# LNA.net
KiCad netlist of a schematic drawn in Altium Designer
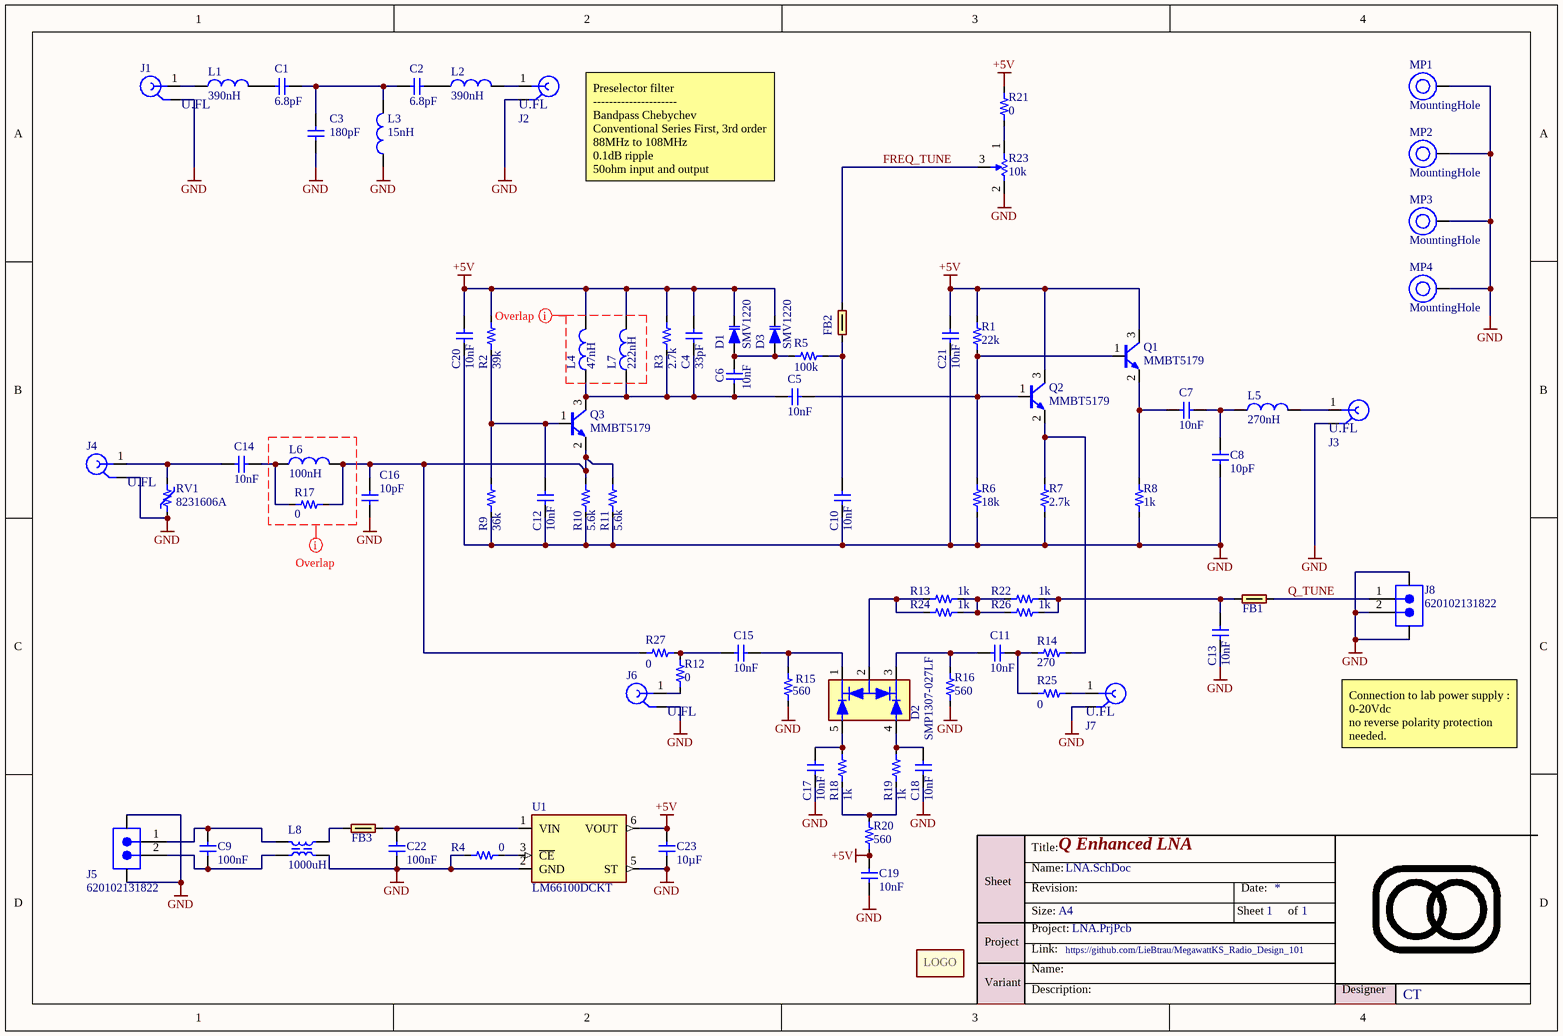
[diagram p0: LNA.SchDoc]

(export (version "E")
  (design (tool "Eeschema 10.0.6"))
  (components
    (comp (ref "C1")
      (value "6.8pF")
      (footprint "0603-C-N")
      (description "WCAP-CSGP Multilayer Ceramic Chip Capacitor, General Purpose, size 0603, NP0, 6.8pF, 50VDC")
      (fields
        (field (name "TOLERANCE") "0.5pF")
        (field (name "Comment") "Capacitor 6.8pF +/-0.5pF 50V NP0 0603")
      )
      (libsource (lib "7c7 Engineering") (part "CAP-NP-2"))
    )
    (comp (ref "C2")
      (value "6.8pF")
      (footprint "0603-C-N")
      (description "WCAP-CSGP Multilayer Ceramic Chip Capacitor, General Purpose, size 0603, NP0, 6.8pF, 50VDC")
      (fields
        (field (name "TOLERANCE") "0.5pF")
        (field (name "Comment") "Capacitor 6.8pF +/-0.5pF 50V NP0 0603")
      )
      (libsource (lib "7c7 Engineering") (part "CAP-NP-2"))
    )
    (comp (ref "C3")
      (value "180pF")
      (footprint "0603-C-N")
      (description "Cap Ceramic 180pF 100V C0G 5% SMD 0603 125°C Paper T/R")
      (fields (field (name "TOLERANCE") "5%") (field (name "JLCPCB PART #") "C107041"))
      (libsource (lib "7c7 Engineering") (part "CAP-NP-2"))
    )
    (comp (ref "C4")
      (value "33pF")
      (footprint "0603-C-N")
      (description "WCAP-CSGP Multilayer Ceramic Chip Capacitor, General Purpose, size 0603, NP0, 33pF, 50VDC")
      (fields (field (name "TOLERANCE") "5%") (field (name "Comment") "Capacitor 33pF +/-5% 50V NP0 0603"))
      (libsource (lib "7c7 Engineering") (part "CAP-NP-2"))
    )
    (comp (ref "C5")
      (value "10nF")
      (footprint "0603-C-N")
      (description "Multilayer Ceramic Capacitor, Grm Series, 0.01 F, 5%, C0g / Np0, 50 V, 0603 [1608 Metric]")
      (fields (field (name "VOLTAGE") "50V") (field (name "TOLERANCE") "5%"))
      (libsource (lib "7c7 Engineering") (part "CAP-NP-2"))
    )
    (comp (ref "C6")
      (value "10nF")
      (footprint "0603-C-N")
      (description "Multilayer Ceramic Capacitor, Grm Series, 0.01 F, 5%, C0g / Np0, 50 V, 0603 [1608 Metric]")
      (fields (field (name "VOLTAGE") "50V") (field (name "TOLERANCE") "5%"))
      (libsource (lib "7c7 Engineering") (part "CAP-NP-2"))
    )
    (comp (ref "C7")
      (value "10nF")
      (footprint "0603-C-N")
      (description "Multilayer Ceramic Capacitor, Grm Series, 0.01 F, 5%, C0g / Np0, 50 V, 0603 [1608 Metric]")
      (fields (field (name "VOLTAGE") "50V") (field (name "TOLERANCE") "5%"))
      (libsource (lib "7c7 Engineering") (part "CAP-NP-2"))
    )
    (comp (ref "C8")
      (value "10pF")
      (footprint "0603-C-N")
      (description "WCAP-CSGP Multilayer Ceramic Chip Capacitor, General Purpose, size 0603, NP0, 10pF, 50VDC")
      (fields (field (name "JLCPCB PART #") "C106245") (field (name "TOLERANCE") "5%"))
      (libsource (lib "7c7 Engineering") (part "CAP-NP-2"))
    )
    (comp (ref "C9")
      (value "100nF")
      (footprint "0603-C-N")
      (description "WCAP-CSGP Multilayer Ceramic Chip Capacitor, General Purpose, size 0603, X7R, 100nF, 50VDC")
      (fields (field (name "TOLERANCE") "10%") (field (name "JLCPCB PART #") "C14663"))
      (libsource (lib "7c7 Engineering") (part "CAP-NP-2"))
    )
    (comp (ref "C10")
      (value "10nF")
      (footprint "0603-C-N")
      (description "Multilayer Ceramic Capacitor, Grm Series, 0.01 F, 5%, C0g / Np0, 50 V, 0603 [1608 Metric]")
      (fields (field (name "VOLTAGE") "50V") (field (name "TOLERANCE") "5%"))
      (libsource (lib "7c7 Engineering") (part "CAP-NP-2"))
    )
    (comp (ref "C11")
      (value "10nF")
      (footprint "0603-C-N")
      (description "Multilayer Ceramic Capacitor, Grm Series, 0.01 F, 5%, C0g / Np0, 50 V, 0603 [1608 Metric]")
      (fields (field (name "VOLTAGE") "50V") (field (name "TOLERANCE") "5%"))
      (libsource (lib "7c7 Engineering") (part "CAP-NP-2"))
    )
    (comp (ref "C12")
      (value "10nF")
      (footprint "0603-C-N")
      (description "Multilayer Ceramic Capacitor, Grm Series, 0.01 F, 5%, C0g / Np0, 50 V, 0603 [1608 Metric]")
      (fields (field (name "VOLTAGE") "50V") (field (name "TOLERANCE") "5%"))
      (libsource (lib "7c7 Engineering") (part "CAP-NP-2"))
    )
    (comp (ref "C13")
      (value "10nF")
      (footprint "0603-C-N")
      (description "Multilayer Ceramic Capacitor, Grm Series, 0.01 F, 5%, C0g / Np0, 50 V, 0603 [1608 Metric]")
      (fields (field (name "VOLTAGE") "50V") (field (name "TOLERANCE") "5%"))
      (libsource (lib "7c7 Engineering") (part "CAP-NP-2"))
    )
    (comp (ref "C14")
      (value "10nF")
      (footprint "0603-C-N")
      (description "Multilayer Ceramic Capacitor, Grm Series, 0.01 F, 5%, C0g / Np0, 50 V, 0603 [1608 Metric]")
      (fields (field (name "VOLTAGE") "50V") (field (name "TOLERANCE") "5%"))
      (libsource (lib "7c7 Engineering") (part "CAP-NP-2"))
    )
    (comp (ref "C15")
      (value "10nF")
      (footprint "0603-C-N")
      (description "Multilayer Ceramic Capacitor, Grm Series, 0.01 F, 5%, C0g / Np0, 50 V, 0603 [1608 Metric]")
      (fields (field (name "VOLTAGE") "50V") (field (name "TOLERANCE") "5%"))
      (libsource (lib "7c7 Engineering") (part "CAP-NP-2"))
    )
    (comp (ref "C16")
      (value "10pF")
      (footprint "0603-C-N")
      (description "WCAP-CSGP Multilayer Ceramic Chip Capacitor, General Purpose, size 0603, NP0, 10pF, 50VDC")
      (fields (field (name "TOLERANCE") "5%") (field (name "JLCPCB PART #") "C106245"))
      (libsource (lib "7c7 Engineering") (part "CAP-NP-2"))
    )
    (comp (ref "C17")
      (value "10nF")
      (footprint "0603-C-N")
      (description "Multilayer Ceramic Capacitor, Grm Series, 0.01 F, 5%, C0g / Np0, 50 V, 0603 [1608 Metric]")
      (fields (field (name "VOLTAGE") "50V") (field (name "TOLERANCE") "5%"))
      (libsource (lib "7c7 Engineering") (part "CAP-NP-2"))
    )
    (comp (ref "C18")
      (value "10nF")
      (footprint "0603-C-N")
      (description "Multilayer Ceramic Capacitor, Grm Series, 0.01 F, 5%, C0g / Np0, 50 V, 0603 [1608 Metric]")
      (fields (field (name "VOLTAGE") "50V") (field (name "TOLERANCE") "5%"))
      (libsource (lib "7c7 Engineering") (part "CAP-NP-2"))
    )
    (comp (ref "C19")
      (value "10nF")
      (footprint "0603-C-N")
      (description "Multilayer Ceramic Capacitor, Grm Series, 0.01 F, 5%, C0g / Np0, 50 V, 0603 [1608 Metric]")
      (fields (field (name "VOLTAGE") "50V") (field (name "TOLERANCE") "5%"))
      (libsource (lib "7c7 Engineering") (part "CAP-NP-2"))
    )
    (comp (ref "C20")
      (value "10nF")
      (footprint "0603-C-N")
      (description "Multilayer Ceramic Capacitor, Grm Series, 0.01 F, 5%, C0g / Np0, 50 V, 0603 [1608 Metric]")
      (fields (field (name "VOLTAGE") "50V") (field (name "TOLERANCE") "5%"))
      (libsource (lib "7c7 Engineering") (part "CAP-NP-2"))
    )
    (comp (ref "C21")
      (value "10nF")
      (footprint "0603-C-N")
      (description "Multilayer Ceramic Capacitor, Grm Series, 0.01 F, 5%, C0g / Np0, 50 V, 0603 [1608 Metric]")
      (fields (field (name "VOLTAGE") "50V") (field (name "TOLERANCE") "5%"))
      (libsource (lib "7c7 Engineering") (part "CAP-NP-2"))
    )
    (comp (ref "C22")
      (value "100nF")
      (footprint "0603-C-N")
      (description "WCAP-CSGP Multilayer Ceramic Chip Capacitor, General Purpose, size 0603, X7R, 100nF, 50VDC")
      (fields (field (name "TOLERANCE") "10%") (field (name "JLCPCB PART #") "C14663"))
      (libsource (lib "7c7 Engineering") (part "CAP-NP-2"))
    )
    (comp (ref "C23")
      (value "10µF")
      (footprint "WCAP-CSGP_1210_L3.2W2.5H2.5")
      (description "WCAP-CSGP Multilayer Ceramic Chip Capacitor, General Purpose, size 1210, X7R, 10µF, 50VDC")
      (fields (field (name "JLCPCB PART #") "C77102") (field (name "TOLERANCE") "10%"))
      (libsource (lib "7c7 Engineering") (part "CAP-NP-2"))
    )
    (comp (ref "D1")
      (value "SMV1220")
      (footprint "FP-SOD523-MFG")
      (description "Diode, Varactor, SC79 N-Type")
      (fields (field (name "Comment") "SMV1220-079LF"))
      (libsource (lib "7c7 Engineering") (part "DIODE-VARACTOR"))
    )
    (comp (ref "D2")
      (value "SMP1307-027LF")
      (footprint "SOT25-N")
      (description "Dio Sw 0.85V 200V 10MA SOT5")
      (libsource (lib "7c7 Engineering") (part "SMP1307-027LF-Symbol-1"))
    )
    (comp (ref "D3")
      (value "SMV1220")
      (footprint "FP-SOD523-MFG")
      (description "Diode, Varactor, SC79 N-Type")
      (fields (field (name "Comment") "SMV1220-079LF"))
      (libsource (lib "7c7 Engineering") (part "DIODE-VARACTOR"))
    )
    (comp (ref "FB1")
      (value "742792662")
      (footprint "0603-FB-N")
      (description "WE-CBF SMT EMI Suppression Ferrite Bead, size 0603, 1000O, 0.83A")
      (fields (field (name "JLCPCB PART #") "C180490") (field (name "MANUFACTURER") "Wurth Elektronik"))
      (libsource (lib "7c7 Engineering") (part "IND_BEAD"))
    )
    (comp (ref "FB2")
      (value "742792662")
      (footprint "0603-FB-N")
      (description "WE-CBF SMT EMI Suppression Ferrite Bead, size 0603, 1000O, 0.83A")
      (fields (field (name "JLCPCB PART #") "C180490") (field (name "MANUFACTURER") "Wurth Elektronik"))
      (libsource (lib "") (part "IND_BEAD_1"))
    )
    (comp (ref "FB3")
      (value "742792662")
      (footprint "0603-FB-N")
      (description "WE-CBF SMT EMI Suppression Ferrite Bead, size 0603, 1000O, 0.83A")
      (fields (field (name "JLCPCB PART #") "C180490") (field (name "MANUFACTURER") "Wurth Elektronik"))
      (libsource (lib "7c7 Engineering") (part "IND_BEAD"))
    )
    (comp (ref "J1")
      (value "U.FL-R-SMT(10)")
      (footprint "HRS-U.FL-R-SMT_V")
      (fields (field (name "JLCPCB PART #") "C88373") (field (name "MANUFACTURER") "Hirose Electric"))
      (libsource (lib "7c7 Engineering") (part "CN_COAX"))
    )
    (comp (ref "J2")
      (value "U.FL-R-SMT(10)")
      (footprint "HRS-U.FL-R-SMT_V")
      (fields (field (name "JLCPCB PART #") "C88373") (field (name "MANUFACTURER") "Hirose Electric"))
      (libsource (lib "") (part "CN_COAX_1"))
    )
    (comp (ref "J3")
      (value "U.FL-R-SMT(10)")
      (footprint "HRS-U.FL-R-SMT_V")
      (fields (field (name "JLCPCB PART #") "C88373") (field (name "MANUFACTURER") "Hirose Electric"))
      (libsource (lib "") (part "CN_COAX_1"))
    )
    (comp (ref "J4")
      (value "U.FL-R-SMT(10)")
      (footprint "HRS-U.FL-R-SMT_V")
      (fields (field (name "JLCPCB PART #") "C88373") (field (name "MANUFACTURER") "Hirose Electric"))
      (libsource (lib "7c7 Engineering") (part "CN_COAX"))
    )
    (comp (ref "J5")
      (value "620102131822")
      (footprint "620102131822")
      (description "WR-WTB SMT Male Horizontal Shrouded Header, pitch 2mm, 2p")
      (fields
        (field (name "JLCPCB PART #") "C295747")
        (field (name "PAGE PART #") "K620102131822")
        (field (name "PUBLISHER") "Wurth Elektronik")
      )
      (libsource (lib "7c7 Engineering") (part "HDR_2P_2MP"))
    )
    (comp (ref "J6")
      (value "U.FL-R-SMT(10)")
      (footprint "HRS-U.FL-R-SMT_V")
      (fields (field (name "JLCPCB PART #") "C88373") (field (name "MANUFACTURER") "Hirose Electric"))
      (libsource (lib "7c7 Engineering") (part "CN_COAX"))
    )
    (comp (ref "J7")
      (value "U.FL-R-SMT(10)")
      (footprint "HRS-U.FL-R-SMT_V")
      (fields (field (name "JLCPCB PART #") "C88373") (field (name "MANUFACTURER") "Hirose Electric"))
      (libsource (lib "") (part "CN_COAX_1"))
    )
    (comp (ref "J8")
      (value "620102131822")
      (footprint "620102131822")
      (description "WR-WTB SMT Male Horizontal Shrouded Header, pitch 2mm, 2p")
      (fields
        (field (name "JLCPCB PART #") "C295747")
        (field (name "PAGE PART #") "K620102131822")
        (field (name "PUBLISHER") "Wurth Elektronik")
      )
      (libsource (lib "7c7 Engineering") (part "HDR_2P_2MP"))
    )
    (comp (ref "L1")
      (value "744762239GA")
      (footprint "WE-KI_1008")
      (description "WE-KI SMT Wire Wound Ceramic Inductor, size 1008, 390nH, 0.47A")
      (fields (field (name "INDUCTANCE") "390nH") (field (name "MANUFACTURER") "Wurth Elektronik"))
      (libsource (lib "7c7 Engineering") (part "IND"))
    )
    (comp (ref "L2")
      (value "744762239GA")
      (footprint "WE-KI_1008")
      (description "WE-KI SMT Wire Wound Ceramic Inductor, size 1008, 390nH, 0.47A")
      (fields (field (name "INDUCTANCE") "390nH") (field (name "MANUFACTURER") "Wurth Elektronik"))
      (libsource (lib "7c7 Engineering") (part "IND"))
    )
    (comp (ref "L3")
      (value "744762115GA")
      (footprint "WE-KI_1008")
      (description "WE-KI SMT Wire Wound Ceramic Inductor, size 1008, 15nH, 1A")
      (fields (field (name "INDUCTANCE") "15nH") (field (name "MANUFACTURER") "Wurth Elektronik"))
      (libsource (lib "7c7 Engineering") (part "IND"))
    )
    (comp (ref "L4")
      (value "744912147")
      (footprint "WE-CAIR_4248")
      (description "WE-CAIR SMT Air Coil, size 4248, 47nH, 3A, 5.6mO")
      (fields (field (name "MANUFACTURER") "Wurth Elektronik") (field (name "INDUCTANCE") "47nH"))
      (libsource (lib "7c7 Engineering") (part "IND"))
    )
    (comp (ref "L5")
      (value "744762227GA")
      (footprint "WE-KI_1008")
      (description "WE-KI SMT Wire Wound Ceramic Inductor, size 1008, 270nH, 0.6A")
      (fields (field (name "MANUFACTURER") "Wurth Elektronik") (field (name "INDUCTANCE") "270nH"))
      (libsource (lib "7c7 Engineering") (part "IND"))
    )
    (comp (ref "L6")
      (value "744762210GA")
      (footprint "WE-KI_1008")
      (description "WE-KI SMT Wire Wound Ceramic Inductor, size 1008, 100nH, 1A")
      (fields (field (name "MANUFACTURER") "Wurth Elektronik") (field (name "INDUCTANCE") "100nH"))
      (libsource (lib "7c7 Engineering") (part "IND"))
    )
    (comp (ref "L7")
      (value "744918222")
      (footprint "WE-CAIR_5910")
      (description "WE-CAIR SMT Air Coil, size 5910, 222nH, 3A, 35mO")
      (fields (field (name "INDUCTANCE") "222nH") (field (name "MANUFACTURER") "Wurth Elektronik"))
      (libsource (lib "7c7 Engineering") (part "IND"))
    )
    (comp (ref "L8")
      (value "744222")
      (footprint "WE-SL2_L9.2W6H5")
      (description "WE-SL2 SMT Common Mode Line Filter, 1000uH, 0.8A, 0.207Ohm")
      (fields
        (field (name "INDUCTANCE") "1000uH")
        (field (name "MANUFACTURER") "Wurth Elektronik")
        (field (name "JLCPCB PART #") "C2829007")
      )
      (libsource (lib "7c7 Engineering") (part "CM-choke"))
    )
    (comp (ref "M1")
      (value "Logo")
      (footprint "LOGO_9x6mm")
      (libsource (lib "Integrated_Library_LieBtrau") (part "Logo"))
    )
    (comp (ref "MP1")
      (value "MountingHole")
      (footprint "PTH-M3D6.5_VIA-RING")
      (libsource (lib "7c7 Engineering") (part "MECH_NO_BOM"))
    )
    (comp (ref "MP2")
      (value "MountingHole")
      (footprint "PTH-M3D6.5_VIA-RING")
      (libsource (lib "7c7 Engineering") (part "MECH_NO_BOM"))
    )
    (comp (ref "MP3")
      (value "MountingHole")
      (footprint "PTH-M3D6.5_VIA-RING")
      (libsource (lib "7c7 Engineering") (part "MECH_NO_BOM"))
    )
    (comp (ref "MP4")
      (value "MountingHole")
      (footprint "PTH-M3D6.5_VIA-RING")
      (libsource (lib "7c7 Engineering") (part "MECH_NO_BOM"))
    )
    (comp (ref "Q1")
      (value "MMBT5179")
      (footprint "SOT-23-3-N")
      (description "MMBT5179 Series 12 V CE Breakdown .05 A NPN RF Transistor - SOT-23")
      (fields (field (name "JLCPCB PART #") "C416012"))
      (libsource (lib "7c7 Engineering") (part "BJT-NPN-BEC"))
    )
    (comp (ref "Q2")
      (value "MMBT5179")
      (footprint "SOT-23-3-N")
      (description "MMBT5179 Series 12 V CE Breakdown .05 A NPN RF Transistor - SOT-23")
      (fields (field (name "JLCPCB PART #") "C416012"))
      (libsource (lib "7c7 Engineering") (part "BJT-NPN-BEC"))
    )
    (comp (ref "Q3")
      (value "MMBT5179")
      (footprint "SOT-23-3-N")
      (description "MMBT5179 Series 12 V CE Breakdown .05 A NPN RF Transistor - SOT-23")
      (fields (field (name "JLCPCB PART #") "C416012"))
      (libsource (lib "7c7 Engineering") (part "BJT-NPN-BEC"))
    )
    (comp (ref "R1")
      (value "22k")
      (footprint "0603-R-N")
      (description "Chip Resistor, Thick Film, General Purpose, 0603, 100mW, 50V, 22 kOhm, +/-1%")
      (fields (field (name "JLCPCB PART #") "C31850") (field (name "TOLERANCE") "1%"))
      (libsource (lib "7c7 Engineering") (part "RES"))
    )
    (comp (ref "R2")
      (value "39k")
      (footprint "0603-R-N")
      (description "Res Thick Film 0603 39K Ohm 1% 0.1W(1/10W) ±100ppm/C Pad SMD T/R")
      (fields (field (name "TOLERANCE") "1%") (field (name "JLCPCB PART #") "C23153"))
      (libsource (lib "7c7 Engineering") (part "RES"))
    )
    (comp (ref "R3")
      (value "2.7k")
      (footprint "0603-R-N")
      (description "Res Thick Film 0603 2.7K Ohm 1% 0.1W(1/10W) ±100ppm/C Pad SMD Automotive T/R")
      (fields (field (name "TOLERANCE") "1%") (field (name "JLCPCB PART #") "C13167"))
      (libsource (lib "7c7 Engineering") (part "RES"))
    )
    (comp (ref "R4")
      (value "0")
      (footprint "0603-R-N")
      (description "Chip Jumper, Thick Film, Jumper, 0603, 100mW, 1A, 0 Ohm, <50 mOhm")
      (fields (field (name "FLIR PART #") "YRES0E-1") (field (name "TOLERANCE") "50 mOhm"))
      (libsource (lib "7c7 Engineering") (part "RES"))
    )
    (comp (ref "R5")
      (value "100k")
      (footprint "0603-R-N")
      (description "Chip Resistor, Thick Film, General Purpose, 0603, 100mW, 50V, 100 kOhm, +/-1%")
      (fields (field (name "TOLERANCE") "1%") (field (name "JLCPCB PART #") "C25803"))
      (libsource (lib "7c7 Engineering") (part "RES"))
    )
    (comp (ref "R6")
      (value "18k")
      (footprint "0603-R-N")
      (description "Chip Resistor, Thick Film, General Purpose, 0603, 100mW, 50V, 18 kOhm, +/-1%")
      (fields (field (name "TOLERANCE") "1%") (field (name "PAGE PART #") "ROQF1802"))
      (libsource (lib "7c7 Engineering") (part "RES"))
    )
    (comp (ref "R7")
      (value "2.7k")
      (footprint "0603-R-N")
      (description "Res Thick Film 0603 2.7K Ohm 1% 0.1W(1/10W) ±100ppm/C Pad SMD Automotive T/R")
      (fields (field (name "TOLERANCE") "1%") (field (name "JLCPCB PART #") "C13167"))
      (libsource (lib "7c7 Engineering") (part "RES"))
    )
    (comp (ref "R8")
      (value "1k")
      (footprint "0603-R-N")
      (description "Chip Resistor, Thick Film, General Purpose, 0603, 100mW, 50V, 1 kOhm, +/-1%")
      (fields (field (name "JLCPCB PART #") "C21190") (field (name "TOLERANCE") "1%"))
      (libsource (lib "7c7 Engineering") (part "RES"))
    )
    (comp (ref "R9")
      (value "36k")
      (footprint "0603-R-N")
      (description "Chip Resistor, Thick Film, General Purpose, 0603, 100mW, 50V, 36 kOhm, +/-1%")
      (fields (field (name "TOLERANCE") "1%") (field (name "JLCPCB PART #") "C23147"))
      (libsource (lib "7c7 Engineering") (part "RES"))
    )
    (comp (ref "R10")
      (value "5.6k")
      (footprint "0603-R-N")
      (description "Res Thick Film 0603 5.6K Ohm 1% 0.1W(1/10W) ±100ppm/C Pad SMD T/R")
      (fields (field (name "JLCPCB PART #") "C23189") (field (name "TOLERANCE") "1%"))
      (libsource (lib "7c7 Engineering") (part "RES"))
    )
    (comp (ref "R11")
      (value "5.6k")
      (footprint "0603-R-N")
      (description "Res Thick Film 0603 5.6K Ohm 1% 0.1W(1/10W) ±100ppm/C Pad SMD T/R")
      (fields (field (name "JLCPCB PART #") "C23189") (field (name "TOLERANCE") "1%"))
      (libsource (lib "7c7 Engineering") (part "RES"))
    )
    (comp (ref "R12")
      (value "0")
      (footprint "0603-R-N")
      (description "Chip Jumper, Thick Film, Jumper, 0603, 100mW, 1A, 0 Ohm, <50 mOhm")
      (fields (field (name "FLIR PART #") "YRES0E-1") (field (name "TOLERANCE") "50 mOhm"))
      (libsource (lib "7c7 Engineering") (part "RES"))
    )
    (comp (ref "R13")
      (value "1k")
      (footprint "0603-R-N")
      (description "Chip Resistor, Thick Film, General Purpose, 0603, 100mW, 50V, 1 kOhm, +/-1%")
      (fields (field (name "JLCPCB PART #") "C21190") (field (name "TOLERANCE") "1%"))
      (libsource (lib "7c7 Engineering") (part "RES"))
    )
    (comp (ref "R14")
      (value "270")
      (footprint "0603-R-N")
      (description "Chip Resistor, Thick Film, General Purpose, 0603, 100mW, 50V, 270 Ohm, +/-1%")
      (fields (field (name "TOLERANCE") "1%") (field (name "JLCPCB PART #") "C22966"))
      (libsource (lib "7c7 Engineering") (part "RES"))
    )
    (comp (ref "R15")
      (value "560")
      (footprint "0603-R-N")
      (description "SMD Chip Resistor, 560 Ohm, ï¿½ 1%, 100 mW, 0603 [1608 Metric], Thick Film, General Purpose")
      (fields (field (name "JLCPCB PART #") "C23204") (field (name "TOLERANCE") "1%"))
      (libsource (lib "7c7 Engineering") (part "RES"))
    )
    (comp (ref "R16")
      (value "560")
      (footprint "0603-R-N")
      (description "SMD Chip Resistor, 560 Ohm, ï¿½ 1%, 100 mW, 0603 [1608 Metric], Thick Film, General Purpose")
      (fields (field (name "JLCPCB PART #") "C23204") (field (name "TOLERANCE") "1%"))
      (libsource (lib "7c7 Engineering") (part "RES"))
    )
    (comp (ref "R17")
      (value "0")
      (footprint "0805-R-N")
      (description "Chip Jumper, Thick Film, Jumper, 0805, 125mW, 2A, 0 Ohm, <50 mOhm")
      (fields (field (name "TOLERANCE") "50 mOhm") (field (name "Comment") "Jumper 0R <50 mOhm 2A 0805"))
      (libsource (lib "7c7 Engineering") (part "RES"))
    )
    (comp (ref "R18")
      (value "1k")
      (footprint "0603-R-N")
      (description "Chip Resistor, Thick Film, General Purpose, 0603, 100mW, 50V, 1 kOhm, +/-1%")
      (fields (field (name "JLCPCB PART #") "C21190") (field (name "TOLERANCE") "1%"))
      (libsource (lib "7c7 Engineering") (part "RES"))
    )
    (comp (ref "R19")
      (value "1k")
      (footprint "0603-R-N")
      (description "Chip Resistor, Thick Film, General Purpose, 0603, 100mW, 50V, 1 kOhm, +/-1%")
      (fields (field (name "JLCPCB PART #") "C21190") (field (name "TOLERANCE") "1%"))
      (libsource (lib "7c7 Engineering") (part "RES"))
    )
    (comp (ref "R20")
      (value "560")
      (footprint "0603-R-N")
      (description "SMD Chip Resistor, 560 Ohm, ï¿½ 1%, 100 mW, 0603 [1608 Metric], Thick Film, General Purpose")
      (fields (field (name "JLCPCB PART #") "C23204") (field (name "TOLERANCE") "1%"))
      (libsource (lib "7c7 Engineering") (part "RES"))
    )
    (comp (ref "R21")
      (value "0")
      (footprint "0603-R-N")
      (description "Chip Jumper, Thick Film, Jumper, 0603, 100mW, 1A, 0 Ohm, <50 mOhm")
      (fields (field (name "FLIR PART #") "YRES0E-1") (field (name "TOLERANCE") "50 mOhm"))
      (libsource (lib "7c7 Engineering") (part "RES"))
    )
    (comp (ref "R22")
      (value "1k")
      (footprint "0603-R-N")
      (description "Chip Resistor, Thick Film, General Purpose, 0603, 100mW, 50V, 1 kOhm, +/-1%")
      (fields (field (name "JLCPCB PART #") "C21190") (field (name "TOLERANCE") "1%"))
      (libsource (lib "7c7 Engineering") (part "RES"))
    )
    (comp (ref "R23")
      (value "10k")
      (footprint "BOUR-3296W")
      (fields
        (field (name "JLCPCB PART #") "C34846")
        (field (name "TOLERANCE") "10%")
        (field (name "Comment") "3296W-1-103LF")
      )
      (libsource (lib "7c7 Engineering") (part "RES-ADJ-3"))
    )
    (comp (ref "R24")
      (value "1k")
      (footprint "0603-R-N")
      (description "Chip Resistor, Thick Film, General Purpose, 0603, 100mW, 50V, 1 kOhm, +/-1%")
      (fields (field (name "JLCPCB PART #") "C21190") (field (name "TOLERANCE") "1%"))
      (libsource (lib "7c7 Engineering") (part "RES"))
    )
    (comp (ref "R25")
      (value "0")
      (footprint "0603-R-N")
      (description "Chip Jumper, Thick Film, Jumper, 0603, 100mW, 1A, 0 Ohm, <50 mOhm")
      (fields (field (name "FLIR PART #") "YRES0E-1") (field (name "TOLERANCE") "50 mOhm"))
      (libsource (lib "7c7 Engineering") (part "RES"))
    )
    (comp (ref "R26")
      (value "1k")
      (footprint "0603-R-N")
      (description "Chip Resistor, Thick Film, General Purpose, 0603, 100mW, 50V, 1 kOhm, +/-1%")
      (fields (field (name "JLCPCB PART #") "C21190") (field (name "TOLERANCE") "1%"))
      (libsource (lib "7c7 Engineering") (part "RES"))
    )
    (comp (ref "R27")
      (value "0")
      (footprint "0603-R-N")
      (description "Chip Jumper, Thick Film, Jumper, 0603, 100mW, 1A, 0 Ohm, <50 mOhm")
      (fields (field (name "FLIR PART #") "YRES0E-1") (field (name "TOLERANCE") "50 mOhm"))
      (libsource (lib "7c7 Engineering") (part "RES"))
    )
    (comp (ref "RV1")
      (value "8231606A")
      (footprint "0603-VAR-N")
      (description "WE-VE femtoF ESD Suppressor, size 0603, 6VDC, 0.05pF")
      (fields (field (name "MANUFACTURER") "Wurth Elektronik"))
      (libsource (lib "7c7 Engineering") (part "RES_VARISTOR"))
    )
    (comp (ref "U1")
      (value "LM66100DCKT")
      (footprint "SOT-363-N")
      (description "1.5-V to 5.5-V, 1.5-A, 0.5-µA IQ ideal diode with integrated FET 6-SC70 -40 to 105")
      (libsource (lib "7c7 Engineering") (part "IC_LM66100"))
    )
  )
  (nets
    (net (code "1") (name "+5V") (class "Default")
      (node (ref "C19") (pin "1") (pinfunction "1_1") (pintype "passive"))
      (node (ref "C20") (pin "1") (pinfunction "1_1") (pintype "passive"))
      (node (ref "C21") (pin "1") (pinfunction "1_1") (pintype "passive"))
      (node (ref "C23") (pin "2") (pinfunction "2_2") (pintype "passive"))
      (node (ref "C4") (pin "2") (pinfunction "2_2") (pintype "passive"))
      (node (ref "D1") (pin "1") (pinfunction "K_1") (pintype "passive"))
      (node (ref "D3") (pin "1") (pinfunction "K_1") (pintype "passive"))
      (node (ref "L4") (pin "2") (pinfunction "2_2") (pintype "passive"))
      (node (ref "L7") (pin "2") (pinfunction "2_2") (pintype "passive"))
      (node (ref "Q1") (pin "3") (pinfunction "C_3") (pintype "passive"))
      (node (ref "Q2") (pin "3") (pinfunction "C_3") (pintype "passive"))
      (node (ref "R1") (pin "2") (pinfunction "2_2") (pintype "passive"))
      (node (ref "R2") (pin "2") (pinfunction "2_2") (pintype "passive"))
      (node (ref "R20") (pin "1") (pinfunction "1_1") (pintype "passive"))
      (node (ref "R21") (pin "2") (pinfunction "2_2") (pintype "passive"))
      (node (ref "R3") (pin "2") (pinfunction "2_2") (pintype "passive"))
      (node (ref "U1") (pin "6") (pinfunction "VOUT_6") (pintype "output"))
    )
    (net (code "2") (name "/FREQ_TUNE") (class "Default")
      (node (ref "FB2") (pin "2") (pinfunction "2_2") (pintype "passive"))
      (node (ref "R23") (pin "3") (pinfunction "TAP_3") (pintype "passive"))
    )
    (net (code "3") (name "/Q_TUNE") (class "Default")
      (node (ref "FB1") (pin "1") (pinfunction "1_1") (pintype "passive"))
      (node (ref "J8") (pin "1") (pinfunction "1_1") (pintype "passive"))
    )
    (net (code "4") (name "GND") (class "Default")
      (node (ref "C10") (pin "2") (pinfunction "2_2") (pintype "passive"))
      (node (ref "C12") (pin "2") (pinfunction "2_2") (pintype "passive"))
      (node (ref "C13") (pin "1") (pinfunction "1_1") (pintype "passive"))
      (node (ref "C16") (pin "1") (pinfunction "1_1") (pintype "passive"))
      (node (ref "C17") (pin "2") (pinfunction "2_2") (pintype "passive"))
      (node (ref "C18") (pin "1") (pinfunction "1_1") (pintype "passive"))
      (node (ref "C19") (pin "2") (pinfunction "2_2") (pintype "passive"))
      (node (ref "C20") (pin "2") (pinfunction "2_2") (pintype "passive"))
      (node (ref "C21") (pin "2") (pinfunction "2_2") (pintype "passive"))
      (node (ref "C22") (pin "1") (pinfunction "1_1") (pintype "passive"))
      (node (ref "C23") (pin "1") (pinfunction "1_1") (pintype "passive"))
      (node (ref "C3") (pin "1") (pinfunction "1_1") (pintype "passive"))
      (node (ref "C8") (pin "2") (pinfunction "2_2") (pintype "passive"))
      (node (ref "J1") (pin "2") (pinfunction "GND_2") (pintype "passive"))
      (node (ref "J2") (pin "2") (pinfunction "GND_2") (pintype "passive"))
      (node (ref "J3") (pin "2") (pinfunction "GND_2") (pintype "passive"))
      (node (ref "J4") (pin "2") (pinfunction "GND_2") (pintype "passive"))
      (node (ref "J5") (pin "MP1") (pinfunction "MP1_MP1") (pintype "passive"))
      (node (ref "J5") (pin "MP2") (pinfunction "MP2_MP2") (pintype "passive"))
      (node (ref "J6") (pin "2") (pinfunction "GND_2") (pintype "passive"))
      (node (ref "J7") (pin "2") (pinfunction "GND_2") (pintype "passive"))
      (node (ref "J8") (pin "2") (pinfunction "2_2") (pintype "passive"))
      (node (ref "J8") (pin "MP1") (pinfunction "MP1_MP1") (pintype "passive"))
      (node (ref "J8") (pin "MP2") (pinfunction "MP2_MP2") (pintype "passive"))
      (node (ref "L3") (pin "1") (pinfunction "1_1") (pintype "passive"))
      (node (ref "L8") (pin "3") (pinfunction "3_3") (pintype "passive"))
      (node (ref "MP1") (pin "1") (pinfunction "H1_1") (pintype "passive"))
      (node (ref "MP2") (pin "1") (pinfunction "H1_1") (pintype "passive"))
      (node (ref "MP3") (pin "1") (pinfunction "H1_1") (pintype "passive"))
      (node (ref "MP4") (pin "1") (pinfunction "H1_1") (pintype "passive"))
      (node (ref "R10") (pin "1") (pinfunction "1_1") (pintype "passive"))
      (node (ref "R11") (pin "1") (pinfunction "1_1") (pintype "passive"))
      (node (ref "R15") (pin "1") (pinfunction "1_1") (pintype "passive"))
      (node (ref "R16") (pin "1") (pinfunction "1_1") (pintype "passive"))
      (node (ref "R23") (pin "2") (pinfunction "B_2") (pintype "passive"))
      (node (ref "R4") (pin "2") (pinfunction "2_2") (pintype "passive"))
      (node (ref "R6") (pin "1") (pinfunction "1_1") (pintype "passive"))
      (node (ref "R7") (pin "1") (pinfunction "1_1") (pintype "passive"))
      (node (ref "R8") (pin "1") (pinfunction "1_1") (pintype "passive"))
      (node (ref "R9") (pin "1") (pinfunction "1_1") (pintype "passive"))
      (node (ref "RV1") (pin "1") (pinfunction "1_1") (pintype "passive"))
      (node (ref "U1") (pin "2") (pinfunction "GND_2") (pintype "power_in"))
      (node (ref "U1") (pin "5") (pinfunction "ST_5") (pintype "output"))
    )
    (net (code "5") (name "Net-(C1-Pad1)") (class "Default")
      (node (ref "C1") (pin "1") (pinfunction "1_1") (pintype "passive"))
      (node (ref "C2") (pin "2") (pinfunction "2_2") (pintype "passive"))
      (node (ref "C3") (pin "2") (pinfunction "2_2") (pintype "passive"))
      (node (ref "L3") (pin "2") (pinfunction "2_2") (pintype "passive"))
    )
    (net (code "6") (name "Net-(C1-Pad2)") (class "Default")
      (node (ref "C1") (pin "2") (pinfunction "2_2") (pintype "passive"))
      (node (ref "L1") (pin "2") (pinfunction "2_2") (pintype "passive"))
    )
    (net (code "7") (name "Net-(C2-Pad1)") (class "Default")
      (node (ref "C2") (pin "1") (pinfunction "1_1") (pintype "passive"))
      (node (ref "L2") (pin "1") (pinfunction "1_1") (pintype "passive"))
    )
    (net (code "8") (name "Net-(C7-Pad2)") (class "Default")
      (node (ref "C7") (pin "2") (pinfunction "2_2") (pintype "passive"))
      (node (ref "C8") (pin "1") (pinfunction "1_1") (pintype "passive"))
      (node (ref "L5") (pin "1") (pinfunction "1_1") (pintype "passive"))
    )
    (net (code "9") (name "Net-(C9-Pad1)") (class "Default")
      (node (ref "C9") (pin "1") (pinfunction "1_1") (pintype "passive"))
      (node (ref "J5") (pin "2") (pinfunction "2_2") (pintype "passive"))
      (node (ref "L8") (pin "4") (pinfunction "4_4") (pintype "passive"))
    )
    (net (code "10") (name "Net-(C9-Pad2)") (class "Default")
      (node (ref "C9") (pin "2") (pinfunction "2_2") (pintype "passive"))
      (node (ref "J5") (pin "1") (pinfunction "1_1") (pintype "passive"))
      (node (ref "L8") (pin "1") (pinfunction "1_1") (pintype "passive"))
    )
    (net (code "11") (name "Net-(C10-Pad1)") (class "Default")
      (node (ref "C10") (pin "1") (pinfunction "1_1") (pintype "passive"))
      (node (ref "FB2") (pin "1") (pinfunction "1_1") (pintype "passive"))
      (node (ref "R5") (pin "2") (pinfunction "2_2") (pintype "passive"))
    )
    (net (code "12") (name "Net-(C11-Pad1)") (class "Default")
      (node (ref "C11") (pin "1") (pinfunction "1_1") (pintype "passive"))
      (node (ref "R14") (pin "1") (pinfunction "1_1") (pintype "passive"))
      (node (ref "R25") (pin "2") (pinfunction "2_2") (pintype "passive"))
    )
    (net (code "13") (name "Net-(C11-Pad2)") (class "Default")
      (node (ref "C11") (pin "2") (pinfunction "2_2") (pintype "passive"))
      (node (ref "D2") (pin "3") (pinfunction "3_3") (pintype "passive"))
      (node (ref "R16") (pin "2") (pinfunction "2_2") (pintype "passive"))
    )
    (net (code "14") (name "Net-(C13-Pad2)") (class "Default")
      (node (ref "C13") (pin "2") (pinfunction "2_2") (pintype "passive"))
      (node (ref "FB1") (pin "2") (pinfunction "2_2") (pintype "passive"))
      (node (ref "R22") (pin "2") (pinfunction "2_2") (pintype "passive"))
      (node (ref "R26") (pin "2") (pinfunction "2_2") (pintype "passive"))
    )
    (net (code "15") (name "Net-(C14-Pad2)") (class "Default")
      (node (ref "C14") (pin "2") (pinfunction "2_2") (pintype "passive"))
      (node (ref "L6") (pin "1") (pinfunction "1_1") (pintype "passive"))
      (node (ref "R17") (pin "1") (pinfunction "1_1") (pintype "passive"))
    )
    (net (code "16") (name "Net-(C15-Pad1)") (class "Default")
      (node (ref "C15") (pin "1") (pinfunction "1_1") (pintype "passive"))
      (node (ref "D2") (pin "1") (pinfunction "1_1") (pintype "passive"))
      (node (ref "R15") (pin "2") (pinfunction "2_2") (pintype "passive"))
    )
    (net (code "17") (name "Net-(C15-Pad2)") (class "Default")
      (node (ref "C15") (pin "2") (pinfunction "2_2") (pintype "passive"))
      (node (ref "R12") (pin "2") (pinfunction "2_2") (pintype "passive"))
      (node (ref "R27") (pin "1") (pinfunction "1_1") (pintype "passive"))
    )
    (net (code "18") (name "Net-(C17-Pad1)") (class "Default")
      (node (ref "C17") (pin "1") (pinfunction "1_1") (pintype "passive"))
      (node (ref "D2") (pin "5") (pinfunction "5_5") (pintype "passive"))
      (node (ref "R18") (pin "1") (pinfunction "1_1") (pintype "passive"))
    )
    (net (code "19") (name "Net-(C18-Pad2)") (class "Default")
      (node (ref "C18") (pin "2") (pinfunction "2_2") (pintype "passive"))
      (node (ref "D2") (pin "4") (pinfunction "4_4") (pintype "passive"))
      (node (ref "R19") (pin "1") (pinfunction "1_1") (pintype "passive"))
    )
    (net (code "20") (name "Net-(D1-A)") (class "Default")
      (node (ref "C6") (pin "1") (pinfunction "1_1") (pintype "passive"))
      (node (ref "D1") (pin "2") (pinfunction "A_2") (pintype "passive"))
      (node (ref "D3") (pin "2") (pinfunction "A_2") (pintype "passive"))
      (node (ref "R5") (pin "1") (pinfunction "1_1") (pintype "passive"))
    )
    (net (code "21") (name "Net-(D2-Pad2)") (class "Default")
      (node (ref "D2") (pin "2") (pinfunction "2_2") (pintype "passive"))
      (node (ref "R13") (pin "1") (pinfunction "1_1") (pintype "passive"))
      (node (ref "R24") (pin "1") (pinfunction "1_1") (pintype "passive"))
    )
    (net (code "22") (name "Net-(FB3-Pad2)") (class "Default")
      (node (ref "FB3") (pin "2") (pinfunction "2_2") (pintype "passive"))
      (node (ref "L8") (pin "2") (pinfunction "2_2") (pintype "passive"))
    )
    (net (code "23") (name "Net-(J1-SIG)") (class "Default")
      (node (ref "J1") (pin "1") (pinfunction "SIG_1") (pintype "passive"))
      (node (ref "L1") (pin "1") (pinfunction "1_1") (pintype "passive"))
    )
    (net (code "24") (name "Net-(J2-SIG)") (class "Default")
      (node (ref "J2") (pin "1") (pinfunction "SIG_1") (pintype "passive"))
      (node (ref "L2") (pin "2") (pinfunction "2_2") (pintype "passive"))
    )
    (net (code "25") (name "Net-(J3-SIG)") (class "Default")
      (node (ref "J3") (pin "1") (pinfunction "SIG_1") (pintype "passive"))
      (node (ref "L5") (pin "2") (pinfunction "2_2") (pintype "passive"))
    )
    (net (code "26") (name "Net-(J4-SIG)") (class "Default")
      (node (ref "C14") (pin "1") (pinfunction "1_1") (pintype "passive"))
      (node (ref "J4") (pin "1") (pinfunction "SIG_1") (pintype "passive"))
      (node (ref "RV1") (pin "2") (pinfunction "2_2") (pintype "passive"))
    )
    (net (code "27") (name "Net-(J6-SIG)") (class "Default")
      (node (ref "J6") (pin "1") (pinfunction "SIG_1") (pintype "passive"))
      (node (ref "R12") (pin "1") (pinfunction "1_1") (pintype "passive"))
    )
    (net (code "28") (name "Net-(J7-SIG)") (class "Default")
      (node (ref "J7") (pin "1") (pinfunction "SIG_1") (pintype "passive"))
      (node (ref "R25") (pin "1") (pinfunction "1_1") (pintype "passive"))
    )
    (net (code "29") (name "Net-(Q1-B)") (class "Default")
      (node (ref "C5") (pin "2") (pinfunction "2_2") (pintype "passive"))
      (node (ref "Q1") (pin "1") (pinfunction "B_1") (pintype "passive"))
      (node (ref "Q2") (pin "1") (pinfunction "B_1") (pintype "passive"))
      (node (ref "R1") (pin "1") (pinfunction "1_1") (pintype "passive"))
      (node (ref "R6") (pin "2") (pinfunction "2_2") (pintype "passive"))
    )
    (net (code "30") (name "Net-(Q1-E)") (class "Default")
      (node (ref "C7") (pin "1") (pinfunction "1_1") (pintype "passive"))
      (node (ref "Q1") (pin "2") (pinfunction "E_2") (pintype "passive"))
      (node (ref "R8") (pin "2") (pinfunction "2_2") (pintype "passive"))
    )
    (net (code "31") (name "Net-(Q2-E)") (class "Default")
      (node (ref "Q2") (pin "2") (pinfunction "E_2") (pintype "passive"))
      (node (ref "R14") (pin "2") (pinfunction "2_2") (pintype "passive"))
      (node (ref "R7") (pin "2") (pinfunction "2_2") (pintype "passive"))
    )
    (net (code "32") (name "Net-(Q3-B)") (class "Default")
      (node (ref "C12") (pin "1") (pinfunction "1_1") (pintype "passive"))
      (node (ref "Q3") (pin "1") (pinfunction "B_1") (pintype "passive"))
      (node (ref "R2") (pin "1") (pinfunction "1_1") (pintype "passive"))
      (node (ref "R9") (pin "2") (pinfunction "2_2") (pintype "passive"))
    )
    (net (code "33") (name "Net-(Q3-C)") (class "Default")
      (node (ref "C4") (pin "1") (pinfunction "1_1") (pintype "passive"))
      (node (ref "C5") (pin "1") (pinfunction "1_1") (pintype "passive"))
      (node (ref "C6") (pin "2") (pinfunction "2_2") (pintype "passive"))
      (node (ref "L4") (pin "1") (pinfunction "1_1") (pintype "passive"))
      (node (ref "L7") (pin "1") (pinfunction "1_1") (pintype "passive"))
      (node (ref "Q3") (pin "3") (pinfunction "C_3") (pintype "passive"))
      (node (ref "R3") (pin "1") (pinfunction "1_1") (pintype "passive"))
    )
    (net (code "34") (name "Net-(Q3-E)") (class "Default")
      (node (ref "C16") (pin "2") (pinfunction "2_2") (pintype "passive"))
      (node (ref "L6") (pin "2") (pinfunction "2_2") (pintype "passive"))
      (node (ref "Q3") (pin "2") (pinfunction "E_2") (pintype "passive"))
      (node (ref "R10") (pin "2") (pinfunction "2_2") (pintype "passive"))
      (node (ref "R11") (pin "2") (pinfunction "2_2") (pintype "passive"))
      (node (ref "R17") (pin "2") (pinfunction "2_2") (pintype "passive"))
      (node (ref "R27") (pin "2") (pinfunction "2_2") (pintype "passive"))
    )
    (net (code "35") (name "Net-(R13-Pad2)") (class "Default")
      (node (ref "R13") (pin "2") (pinfunction "2_2") (pintype "passive"))
      (node (ref "R22") (pin "1") (pinfunction "1_1") (pintype "passive"))
      (node (ref "R24") (pin "2") (pinfunction "2_2") (pintype "passive"))
      (node (ref "R26") (pin "1") (pinfunction "1_1") (pintype "passive"))
    )
    (net (code "36") (name "Net-(R18-Pad2)") (class "Default")
      (node (ref "R18") (pin "2") (pinfunction "2_2") (pintype "passive"))
      (node (ref "R19") (pin "2") (pinfunction "2_2") (pintype "passive"))
      (node (ref "R20") (pin "2") (pinfunction "2_2") (pintype "passive"))
    )
    (net (code "37") (name "Net-(R23-A)") (class "Default")
      (node (ref "R21") (pin "1") (pinfunction "1_1") (pintype "passive"))
      (node (ref "R23") (pin "1") (pinfunction "A_1") (pintype "passive"))
    )
    (net (code "38") (name "Net-(U1-VIN)") (class "Default")
      (node (ref "C22") (pin "2") (pinfunction "2_2") (pintype "passive"))
      (node (ref "FB3") (pin "1") (pinfunction "1_1") (pintype "passive"))
      (node (ref "U1") (pin "1") (pinfunction "VIN_1") (pintype "power_in"))
    )
    (net (code "39") (name "Net-(U1-~{CE})") (class "Default")
      (node (ref "R4") (pin "1") (pinfunction "1_1") (pintype "passive"))
      (node (ref "U1") (pin "3") (pinfunction "~{CE}_3") (pintype "input"))
    )
  )
)
